# PIXRACER-SERIALS-R12.net
KiCad netlist of a schematic drawn in Altium Designer
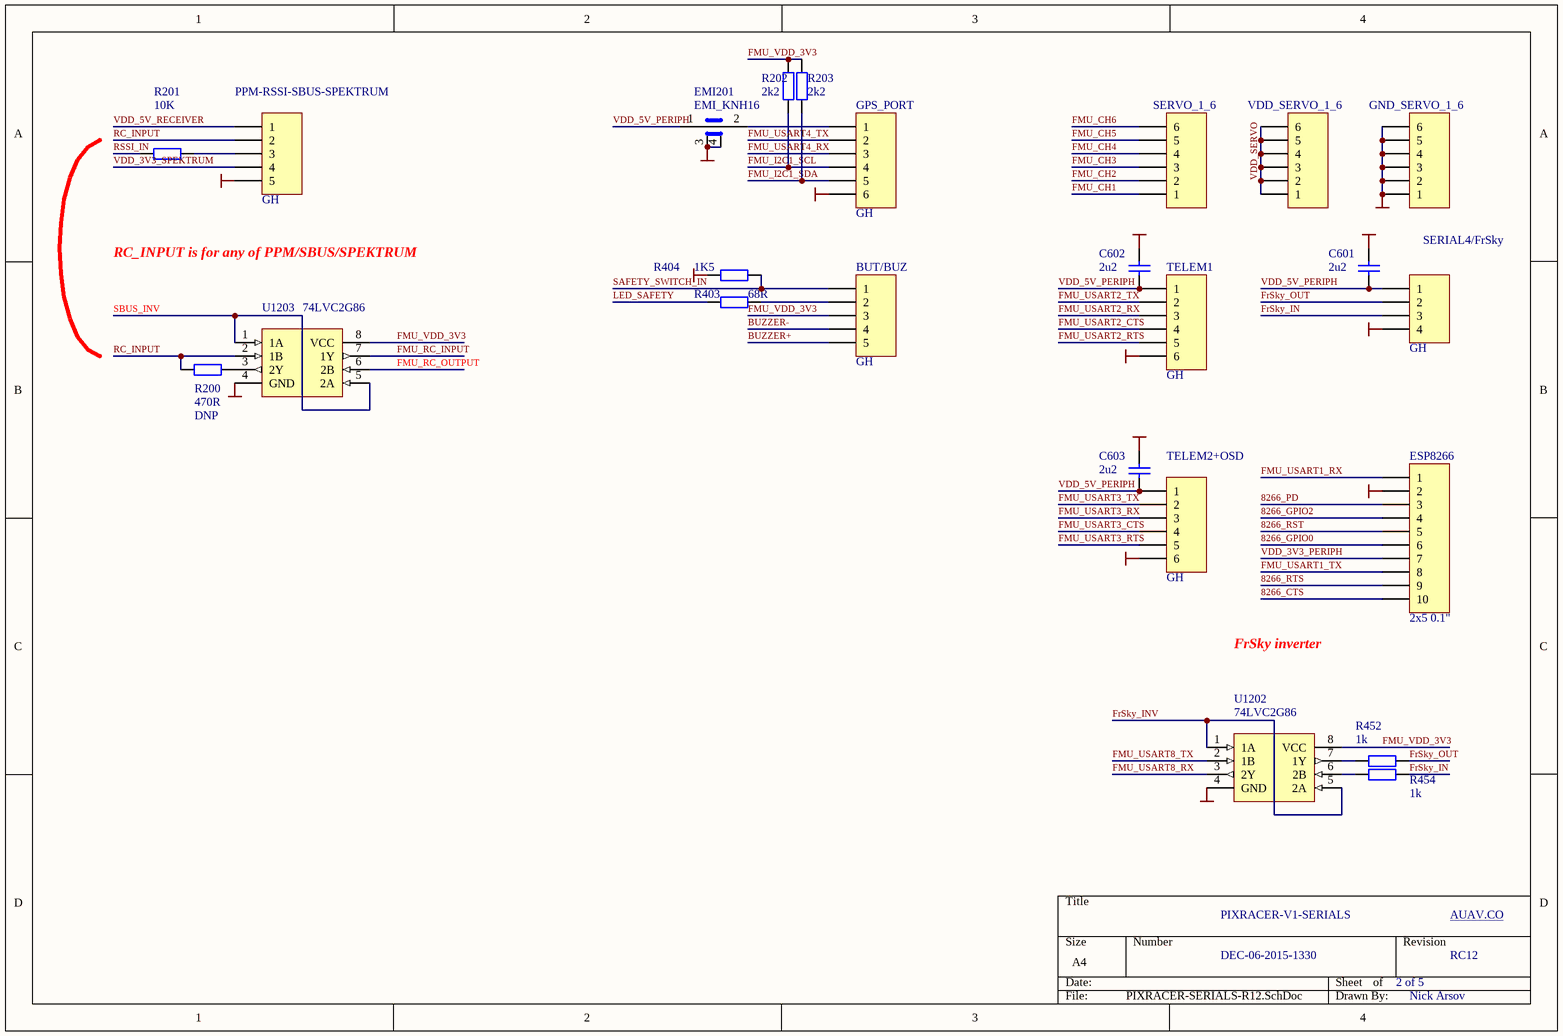
[diagram p0: PIXRACER-SERIALS-R12.SchDoc]

(export (version "E")
  (design (tool "Eeschema 10.0.6"))
  (components
    (comp (ref "BUT/BUZ")
      (value "GH")
      (footprint "Molex_Clik_1.25_5H")
      (description "Header, 5-Pin")
      (fields (field (name "PUBLISHER") "Altium Limited"))
      (libsource (lib "Miscellaneous Connectors") (part "Header 5"))
    )
    (comp (ref "C601")
      (value "2u2")
      (footprint "0402A")
      (description "Capacitor")
      (fields (field (name "PUBLISHER") "Altium Limited"))
      (libsource (lib "Miscellaneous Devices") (part "Cap"))
    )
    (comp (ref "C602")
      (value "2u2")
      (footprint "0402A")
      (description "Capacitor")
      (fields (field (name "PUBLISHER") "Altium Limited"))
      (libsource (lib "Miscellaneous Devices") (part "Cap"))
    )
    (comp (ref "C603")
      (value "2u2")
      (footprint "0402A")
      (description "Capacitor")
      (fields (field (name "PUBLISHER") "Altium Limited"))
      (libsource (lib "Miscellaneous Devices") (part "Cap"))
    )
    (comp (ref "EMI201")
      (value "EMI_KNH16")
      (footprint "EMI_KNH16_0603")
      (libsource (lib "My_Altium") (part "EMI_KNH16"))
    )
    (comp (ref "ESP8266")
      (value "2x5 0.1\"")
      (footprint "2.54mm_10pin_SMD")
      (description "Header, 10-Pin")
      (fields (field (name "PUBLISHER") "Altium Limited"))
      (libsource (lib "Miscellaneous Connectors") (part "Header 10"))
    )
    (comp (ref "GND_SERVO_1_6")
      (value "Header 6")
      (footprint "HDR1X6")
      (description "Header, 6-Pin")
      (fields (field (name "PUBLISHER") "Altium Limited"))
      (libsource (lib "Miscellaneous Connectors") (part "Header 6"))
    )
    (comp (ref "GPS_PORT")
      (value "GH")
      (footprint "Molex_Clok_1.25_6H")
      (description "Header, 6-Pin")
      (fields (field (name "PUBLISHER") "Altium Limited"))
      (libsource (lib "") (part "Header 6_1"))
    )
    (comp (ref "PPM-RSSI-SBUS-SPEKTRUM")
      (value "GH")
      (footprint "Molex_Clik_1.25_5H")
      (description "Header, 5-Pin")
      (fields (field (name "PUBLISHER") "Altium Limited"))
      (libsource (lib "Miscellaneous Connectors") (part "Header 5"))
    )
    (comp (ref "R200")
      (value "470R")
      (footprint "0402A")
      (description "Resistor")
      (fields (field (name "REM") "DNP") (field (name "PUBLISHER") "Altium Limited"))
      (libsource (lib "Miscellaneous Devices") (part "Res2"))
    )
    (comp (ref "R201")
      (value "10K")
      (footprint "0402A")
      (description "Resistor")
      (fields (field (name "PUBLISHER") "Altium Limited"))
      (libsource (lib "Miscellaneous Devices") (part "Res2"))
    )
    (comp (ref "R202")
      (value "2k2")
      (footprint "0402A")
      (description "Resistor")
      (fields (field (name "PUBLISHER") "Altium Limited"))
      (libsource (lib "") (part "Res2_1"))
    )
    (comp (ref "R203")
      (value "2k2")
      (footprint "0402A")
      (description "Resistor")
      (fields (field (name "PUBLISHER") "Altium Limited"))
      (libsource (lib "") (part "Res2_1"))
    )
    (comp (ref "R403")
      (value "68R")
      (footprint "0402A")
      (description "Resistor")
      (fields (field (name "PUBLISHER") "Altium Limited"))
      (libsource (lib "Miscellaneous Devices") (part "Res2"))
    )
    (comp (ref "R404")
      (value "1K5")
      (footprint "0402A")
      (description "Resistor")
      (fields (field (name "PUBLISHER") "Altium Limited"))
      (libsource (lib "Miscellaneous Devices") (part "Res2"))
    )
    (comp (ref "R452")
      (value "1k")
      (footprint "0402A")
      (description "Resistor")
      (fields (field (name "PUBLISHER") "Altium Limited"))
      (libsource (lib "Miscellaneous Devices") (part "Res2"))
    )
    (comp (ref "R454")
      (value "1k")
      (footprint "0402A")
      (description "Resistor")
      (fields (field (name "PUBLISHER") "Altium Limited"))
      (libsource (lib "Miscellaneous Devices") (part "Res2"))
    )
    (comp (ref "SERIAL4/FrSky")
      (value "GH")
      (footprint "Molex_1.25_click_4")
      (description "Header, 4-Pin")
      (fields (field (name "PUBLISHER") "Altium Limited"))
      (libsource (lib "Miscellaneous Connectors") (part "Header 4"))
    )
    (comp (ref "SERVO_1_6")
      (value "Header 6")
      (footprint "HDR1X6")
      (description "Header, 6-Pin")
      (fields (field (name "PUBLISHER") "Altium Limited"))
      (libsource (lib "Miscellaneous Connectors") (part "Header 6"))
    )
    (comp (ref "TELEM1")
      (value "GH")
      (footprint "Molex_Clok_1.25_6H")
      (description "Header, 6-Pin")
      (fields (field (name "PUBLISHER") "Altium Limited"))
      (libsource (lib "") (part "Header 6_1"))
    )
    (comp (ref "TELEM2+OSD")
      (value "GH")
      (footprint "Molex_Clok_1.25_6H")
      (description "Header, 6-Pin")
      (fields (field (name "PUBLISHER") "Altium Limited"))
      (libsource (lib "") (part "Header 6_1"))
    )
    (comp (ref "U1202")
      (value "74LVC2G86")
      (footprint "DCU(SM-8)")
      (libsource (lib "My_Altium") (part "74LVC2G86"))
    )
    (comp (ref "U1203")
      (value "74LVC2G86")
      (footprint "DCU(SM-8)")
      (libsource (lib "My_Altium") (part "74LVC2G86"))
    )
    (comp (ref "VDD_SERVO_1_6")
      (value "Header 6")
      (footprint "HDR1X6")
      (description "Header, 6-Pin")
      (fields (field (name "PUBLISHER") "Altium Limited"))
      (libsource (lib "Miscellaneous Connectors") (part "Header 6"))
    )
  )
  (nets
    (net (code "1") (name "/8266_CTS") (class "Default")
      (node (ref "ESP8266") (pin "10") (pinfunction "10_10") (pintype "passive"))
    )
    (net (code "2") (name "/8266_GPIO0") (class "Default")
      (node (ref "ESP8266") (pin "6") (pinfunction "6_6") (pintype "passive"))
    )
    (net (code "3") (name "/8266_GPIO2") (class "Default")
      (node (ref "ESP8266") (pin "4") (pinfunction "4_4") (pintype "passive"))
    )
    (net (code "4") (name "/8266_PD") (class "Default")
      (node (ref "ESP8266") (pin "3") (pinfunction "3_3") (pintype "passive"))
    )
    (net (code "5") (name "/8266_RST") (class "Default")
      (node (ref "ESP8266") (pin "5") (pinfunction "5_5") (pintype "passive"))
    )
    (net (code "6") (name "/8266_RTS") (class "Default")
      (node (ref "ESP8266") (pin "9") (pinfunction "9_9") (pintype "passive"))
    )
    (net (code "7") (name "/BUZZER+") (class "Default")
      (node (ref "BUT/BUZ") (pin "5") (pinfunction "5_5") (pintype "passive"))
    )
    (net (code "8") (name "/BUZZER-") (class "Default")
      (node (ref "BUT/BUZ") (pin "4") (pinfunction "4_4") (pintype "passive"))
    )
    (net (code "9") (name "/FMU_CH1") (class "Default")
      (node (ref "SERVO_1_6") (pin "1") (pinfunction "1_1") (pintype "passive"))
    )
    (net (code "10") (name "/FMU_CH2") (class "Default")
      (node (ref "SERVO_1_6") (pin "2") (pinfunction "2_2") (pintype "passive"))
    )
    (net (code "11") (name "/FMU_CH3") (class "Default")
      (node (ref "SERVO_1_6") (pin "3") (pinfunction "3_3") (pintype "passive"))
    )
    (net (code "12") (name "/FMU_CH4") (class "Default")
      (node (ref "SERVO_1_6") (pin "4") (pinfunction "4_4") (pintype "passive"))
    )
    (net (code "13") (name "/FMU_CH5") (class "Default")
      (node (ref "SERVO_1_6") (pin "5") (pinfunction "5_5") (pintype "passive"))
    )
    (net (code "14") (name "/FMU_CH6") (class "Default")
      (node (ref "SERVO_1_6") (pin "6") (pinfunction "6_6") (pintype "passive"))
    )
    (net (code "15") (name "/FMU_I2C1_SCL") (class "Default")
      (node (ref "GPS_PORT") (pin "4") (pinfunction "4_4") (pintype "passive"))
      (node (ref "R202") (pin "2") (pinfunction "2_2") (pintype "passive"))
    )
    (net (code "16") (name "/FMU_I2C1_SDA") (class "Default")
      (node (ref "GPS_PORT") (pin "5") (pinfunction "5_5") (pintype "passive"))
      (node (ref "R203") (pin "2") (pinfunction "2_2") (pintype "passive"))
    )
    (net (code "17") (name "/FMU_RC_INPUT") (class "Default")
      (node (ref "U1203") (pin "7") (pinfunction "1Y_7") (pintype "output"))
    )
    (net (code "18") (name "/FMU_RC_OUTPUT") (class "Default")
      (node (ref "U1203") (pin "6") (pinfunction "2B_6") (pintype "input"))
    )
    (net (code "19") (name "/FMU_USART1_RX") (class "Default")
      (node (ref "ESP8266") (pin "1") (pinfunction "1_1") (pintype "passive"))
    )
    (net (code "20") (name "/FMU_USART1_TX") (class "Default")
      (node (ref "ESP8266") (pin "8") (pinfunction "8_8") (pintype "passive"))
    )
    (net (code "21") (name "/FMU_USART2_CTS") (class "Default")
      (node (ref "TELEM1") (pin "4") (pinfunction "4_4") (pintype "passive"))
    )
    (net (code "22") (name "/FMU_USART2_RTS") (class "Default")
      (node (ref "TELEM1") (pin "5") (pinfunction "5_5") (pintype "passive"))
    )
    (net (code "23") (name "/FMU_USART2_RX") (class "Default")
      (node (ref "TELEM1") (pin "3") (pinfunction "3_3") (pintype "passive"))
    )
    (net (code "24") (name "/FMU_USART2_TX") (class "Default")
      (node (ref "TELEM1") (pin "2") (pinfunction "2_2") (pintype "passive"))
    )
    (net (code "25") (name "/FMU_USART3_CTS") (class "Default")
      (node (ref "TELEM2+OSD") (pin "4") (pinfunction "4_4") (pintype "passive"))
    )
    (net (code "26") (name "/FMU_USART3_RTS") (class "Default")
      (node (ref "TELEM2+OSD") (pin "5") (pinfunction "5_5") (pintype "passive"))
    )
    (net (code "27") (name "/FMU_USART3_RX") (class "Default")
      (node (ref "TELEM2+OSD") (pin "3") (pinfunction "3_3") (pintype "passive"))
    )
    (net (code "28") (name "/FMU_USART3_TX") (class "Default")
      (node (ref "TELEM2+OSD") (pin "2") (pinfunction "2_2") (pintype "passive"))
    )
    (net (code "29") (name "/FMU_USART4_RX") (class "Default")
      (node (ref "GPS_PORT") (pin "3") (pinfunction "3_3") (pintype "passive"))
    )
    (net (code "30") (name "/FMU_USART4_TX") (class "Default")
      (node (ref "GPS_PORT") (pin "2") (pinfunction "2_2") (pintype "passive"))
    )
    (net (code "31") (name "/FMU_USART8_RX") (class "Default")
      (node (ref "U1202") (pin "3") (pinfunction "2Y_3") (pintype "output"))
    )
    (net (code "32") (name "/FMU_USART8_TX") (class "Default")
      (node (ref "U1202") (pin "2") (pinfunction "1B_2") (pintype "input"))
    )
    (net (code "33") (name "/FMU_VDD_3V3") (class "Default")
      (node (ref "BUT/BUZ") (pin "3") (pinfunction "3_3") (pintype "passive"))
      (node (ref "R202") (pin "1") (pinfunction "1_1") (pintype "passive"))
      (node (ref "R203") (pin "1") (pinfunction "1_1") (pintype "passive"))
      (node (ref "U1202") (pin "8") (pinfunction "VCC_8") (pintype "passive"))
      (node (ref "U1203") (pin "8") (pinfunction "VCC_8") (pintype "passive"))
    )
    (net (code "34") (name "/FrSky_IN") (class "Default")
      (node (ref "R454") (pin "1") (pinfunction "1_1") (pintype "passive"))
      (node (ref "SERIAL4/FrSky") (pin "3") (pinfunction "3_3") (pintype "passive"))
    )
    (net (code "35") (name "/FrSky_INV") (class "Default")
      (node (ref "U1202") (pin "1") (pinfunction "1A_1") (pintype "input"))
      (node (ref "U1202") (pin "5") (pinfunction "2A_5") (pintype "input"))
    )
    (net (code "36") (name "/FrSky_OUT") (class "Default")
      (node (ref "R452") (pin "1") (pinfunction "1_1") (pintype "passive"))
      (node (ref "SERIAL4/FrSky") (pin "2") (pinfunction "2_2") (pintype "passive"))
    )
    (net (code "37") (name "/LED_SAFETY") (class "Default")
      (node (ref "R403") (pin "2") (pinfunction "2_2") (pintype "passive"))
    )
    (net (code "38") (name "/RC_INPUT") (class "Default")
      (node (ref "PPM-RSSI-SBUS-SPEKTRUM") (pin "2") (pinfunction "2_2") (pintype "passive"))
      (node (ref "R200") (pin "2") (pinfunction "2_2") (pintype "passive"))
      (node (ref "U1203") (pin "2") (pinfunction "1B_2") (pintype "input"))
    )
    (net (code "39") (name "/RSSI_IN") (class "Default")
      (node (ref "R201") (pin "2") (pinfunction "2_2") (pintype "passive"))
    )
    (net (code "40") (name "/SAFETY_SWITCH_IN") (class "Default")
      (node (ref "BUT/BUZ") (pin "1") (pinfunction "1_1") (pintype "passive"))
      (node (ref "R404") (pin "1") (pinfunction "1_1") (pintype "passive"))
    )
    (net (code "41") (name "/SBUS_INV") (class "Default")
      (node (ref "U1203") (pin "1") (pinfunction "1A_1") (pintype "input"))
      (node (ref "U1203") (pin "5") (pinfunction "2A_5") (pintype "input"))
    )
    (net (code "42") (name "/VDD_3V3_PERIPH") (class "Default")
      (node (ref "ESP8266") (pin "7") (pinfunction "7_7") (pintype "passive"))
    )
    (net (code "43") (name "/VDD_3V3_SPEKTRUM") (class "Default")
      (node (ref "PPM-RSSI-SBUS-SPEKTRUM") (pin "4") (pinfunction "4_4") (pintype "passive"))
    )
    (net (code "44") (name "/VDD_5V_PERIPH") (class "Default")
      (node (ref "C601") (pin "1") (pinfunction "1_1") (pintype "passive"))
      (node (ref "C602") (pin "1") (pinfunction "1_1") (pintype "passive"))
      (node (ref "C603") (pin "1") (pinfunction "1_1") (pintype "passive"))
      (node (ref "EMI201") (pin "1") (pinfunction "L1_1") (pintype "passive"))
      (node (ref "SERIAL4/FrSky") (pin "1") (pinfunction "1_1") (pintype "passive"))
      (node (ref "TELEM1") (pin "1") (pinfunction "1_1") (pintype "passive"))
      (node (ref "TELEM2+OSD") (pin "1") (pinfunction "1_1") (pintype "passive"))
    )
    (net (code "45") (name "/VDD_5V_RECEIVER") (class "Default")
      (node (ref "PPM-RSSI-SBUS-SPEKTRUM") (pin "1") (pinfunction "1_1") (pintype "passive"))
    )
    (net (code "46") (name "/VDD_SERVO") (class "Default")
      (node (ref "VDD_SERVO_1_6") (pin "1") (pinfunction "1_1") (pintype "passive"))
      (node (ref "VDD_SERVO_1_6") (pin "2") (pinfunction "2_2") (pintype "passive"))
      (node (ref "VDD_SERVO_1_6") (pin "3") (pinfunction "3_3") (pintype "passive"))
      (node (ref "VDD_SERVO_1_6") (pin "4") (pinfunction "4_4") (pintype "passive"))
      (node (ref "VDD_SERVO_1_6") (pin "5") (pinfunction "5_5") (pintype "passive"))
      (node (ref "VDD_SERVO_1_6") (pin "6") (pinfunction "6_6") (pintype "passive"))
    )
    (net (code "47") (name "GND") (class "Default")
      (node (ref "C601") (pin "2") (pinfunction "2_2") (pintype "passive"))
      (node (ref "C602") (pin "2") (pinfunction "2_2") (pintype "passive"))
      (node (ref "C603") (pin "2") (pinfunction "2_2") (pintype "passive"))
      (node (ref "EMI201") (pin "3") (pinfunction "G_3") (pintype "power_in"))
      (node (ref "EMI201") (pin "4") (pinfunction "G_4") (pintype "passive"))
      (node (ref "ESP8266") (pin "2") (pinfunction "2_2") (pintype "passive"))
      (node (ref "GND_SERVO_1_6") (pin "1") (pinfunction "1_1") (pintype "passive"))
      (node (ref "GND_SERVO_1_6") (pin "2") (pinfunction "2_2") (pintype "passive"))
      (node (ref "GND_SERVO_1_6") (pin "3") (pinfunction "3_3") (pintype "passive"))
      (node (ref "GND_SERVO_1_6") (pin "4") (pinfunction "4_4") (pintype "passive"))
      (node (ref "GND_SERVO_1_6") (pin "5") (pinfunction "5_5") (pintype "passive"))
      (node (ref "GND_SERVO_1_6") (pin "6") (pinfunction "6_6") (pintype "passive"))
      (node (ref "GPS_PORT") (pin "6") (pinfunction "6_6") (pintype "passive"))
      (node (ref "PPM-RSSI-SBUS-SPEKTRUM") (pin "5") (pinfunction "5_5") (pintype "passive"))
      (node (ref "R404") (pin "2") (pinfunction "2_2") (pintype "passive"))
      (node (ref "SERIAL4/FrSky") (pin "4") (pinfunction "4_4") (pintype "passive"))
      (node (ref "TELEM1") (pin "6") (pinfunction "6_6") (pintype "passive"))
      (node (ref "TELEM2+OSD") (pin "6") (pinfunction "6_6") (pintype "passive"))
      (node (ref "U1202") (pin "4") (pinfunction "GND_4") (pintype "passive"))
      (node (ref "U1203") (pin "4") (pinfunction "GND_4") (pintype "passive"))
    )
    (net (code "48") (name "Net-(BUT/BUZ-Pad2)") (class "Default")
      (node (ref "BUT/BUZ") (pin "2") (pinfunction "2_2") (pintype "passive"))
      (node (ref "R403") (pin "1") (pinfunction "1_1") (pintype "passive"))
    )
    (net (code "49") (name "Net-(EMI201-L2)") (class "Default")
      (node (ref "EMI201") (pin "2") (pinfunction "L2_2") (pintype "passive"))
      (node (ref "GPS_PORT") (pin "1") (pinfunction "1_1") (pintype "passive"))
    )
    (net (code "50") (name "Net-(PPM-RSSI-SBUS-SPEKTRUM-Pad3)") (class "Default")
      (node (ref "PPM-RSSI-SBUS-SPEKTRUM") (pin "3") (pinfunction "3_3") (pintype "passive"))
      (node (ref "R201") (pin "1") (pinfunction "1_1") (pintype "passive"))
    )
    (net (code "51") (name "Net-(U1202-1Y)") (class "Default")
      (node (ref "R452") (pin "2") (pinfunction "2_2") (pintype "passive"))
      (node (ref "U1202") (pin "7") (pinfunction "1Y_7") (pintype "output"))
    )
    (net (code "52") (name "Net-(U1202-2B)") (class "Default")
      (node (ref "R454") (pin "2") (pinfunction "2_2") (pintype "passive"))
      (node (ref "U1202") (pin "6") (pinfunction "2B_6") (pintype "input"))
    )
    (net (code "53") (name "Net-(U1203-2Y)") (class "Default")
      (node (ref "R200") (pin "1") (pinfunction "1_1") (pintype "passive"))
      (node (ref "U1203") (pin "3") (pinfunction "2Y_3") (pintype "output"))
    )
  )
)
